# 13thISE_ver6.net
KiCad netlist of a schematic drawn in EAGLE
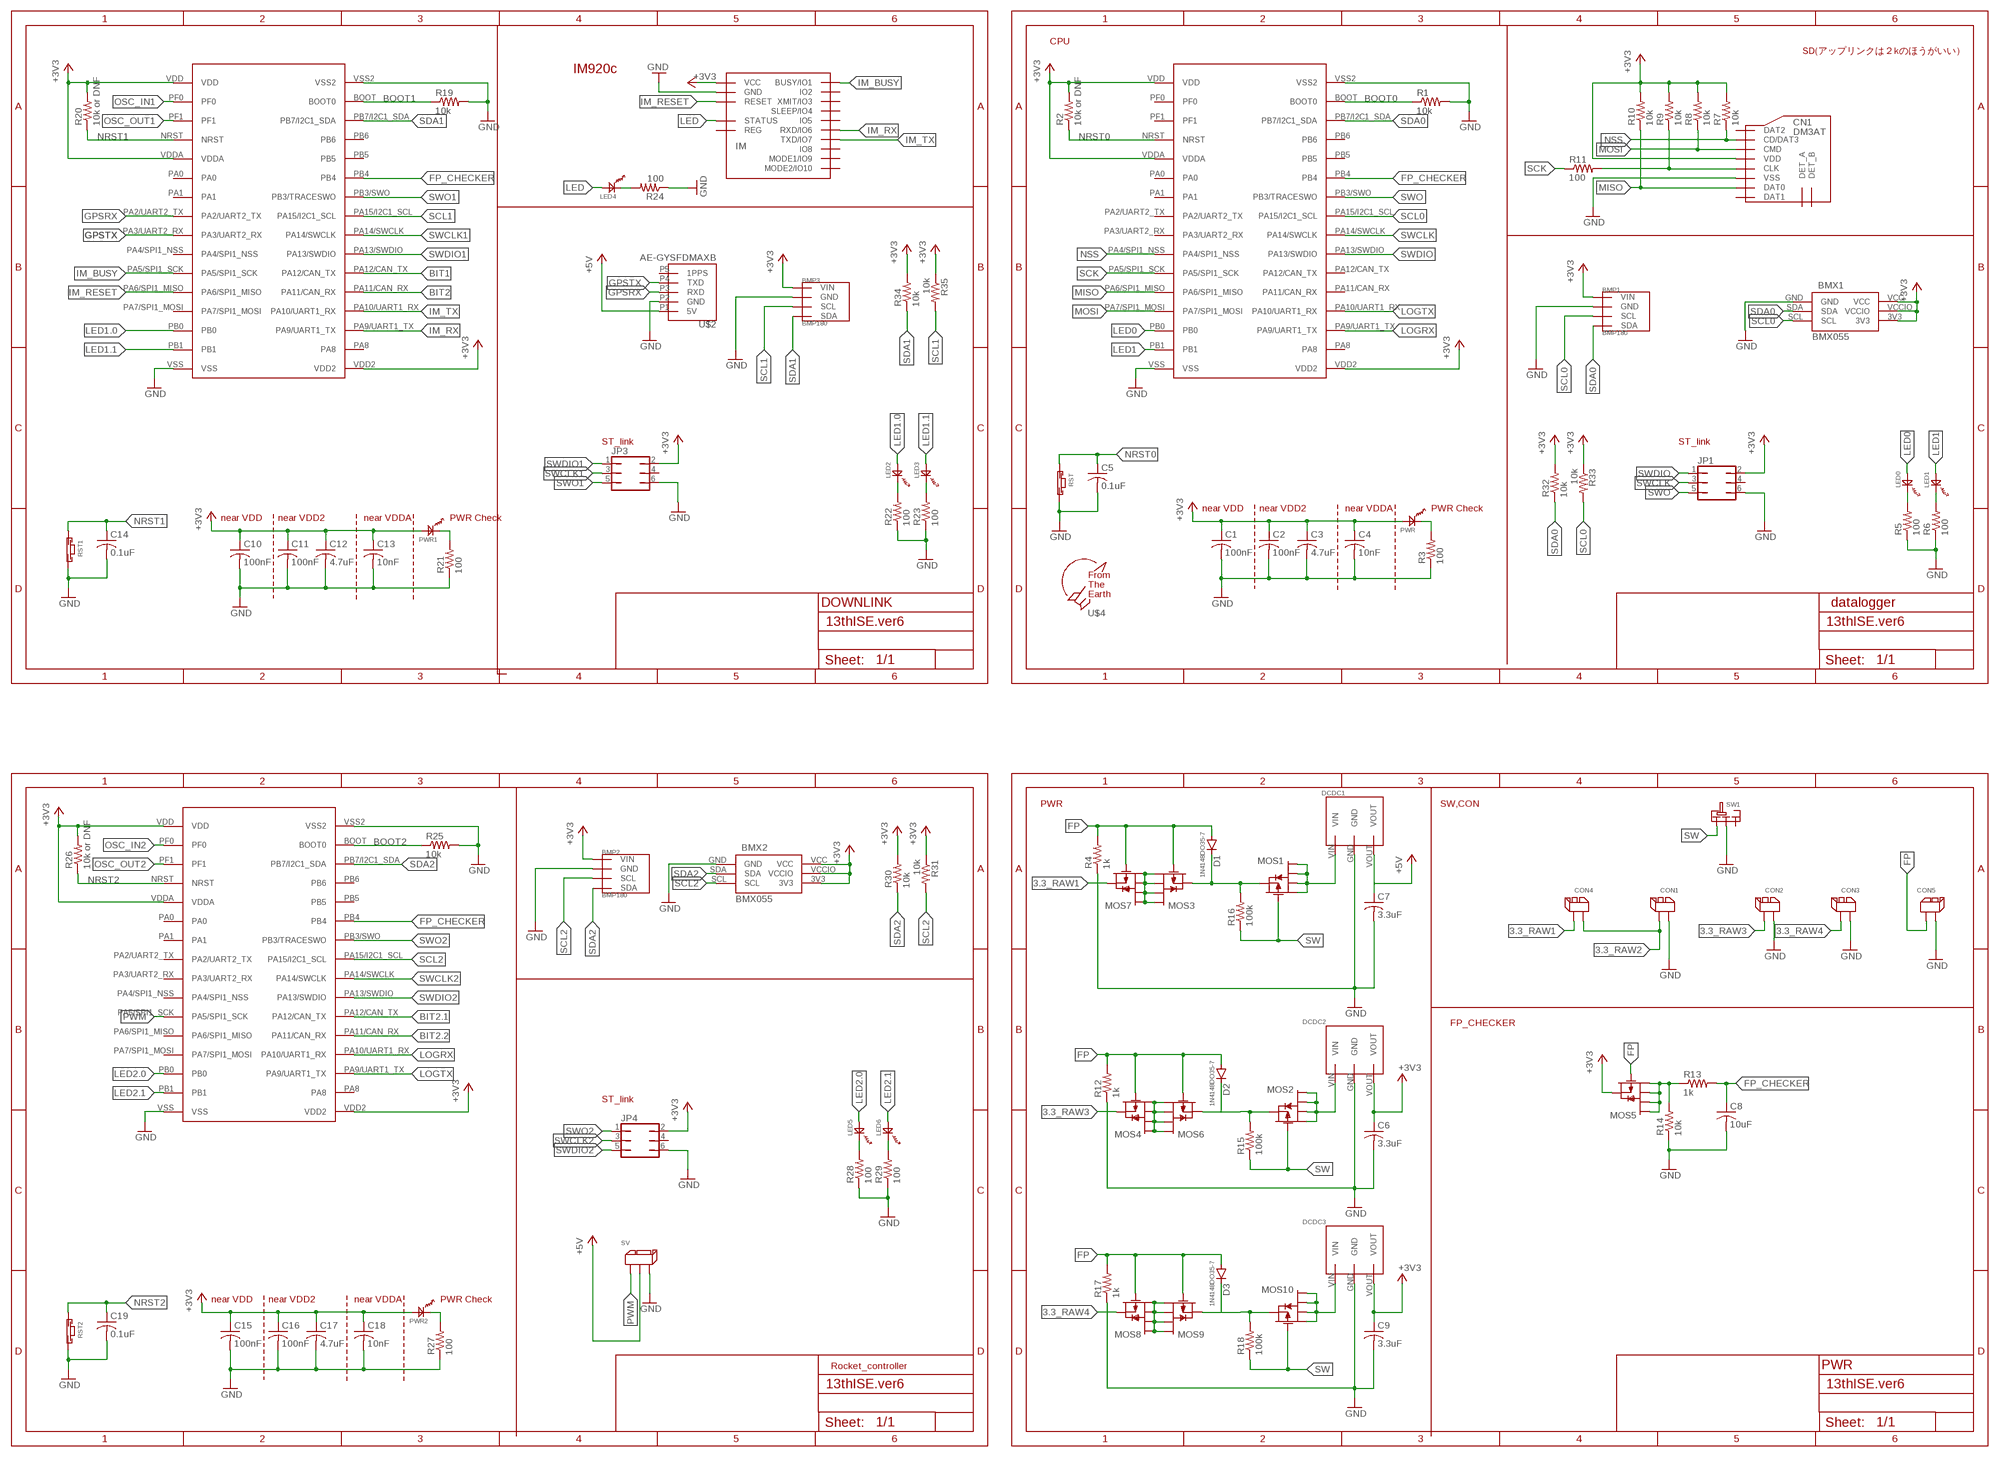
[diagram p0: schematic, sheet 1]

(export (version "E")
  (design (tool "Eeschema 10.0.6"))
  (components
    (comp (ref "BMP1")
      (value "BMP180")
      (footprint "eagle-import:GY-68")
      (libsource (lib "eagle-import") (part "BMP180"))
    )
    (comp (ref "BMP2")
      (value "BMP180")
      (footprint "eagle-import:GY-68")
      (libsource (lib "eagle-import") (part "BMP180"))
    )
    (comp (ref "BMP3")
      (value "BMP180")
      (footprint "eagle-import:GY-68")
      (libsource (lib "eagle-import") (part "BMP180"))
    )
    (comp (ref "BMX1")
      (value "BMX055")
      (footprint "eagle-import:BMX055")
      (libsource (lib "eagle-import") (part "BMX055"))
    )
    (comp (ref "BMX2")
      (value "BMX055")
      (footprint "eagle-import:BMX055")
      (libsource (lib "eagle-import") (part "BMX055"))
    )
    (comp (ref "C1")
      (value "100nF")
      (footprint "eagle-import:C1608")
      (libsource (lib "eagle-import") (part "C-USC1608"))
    )
    (comp (ref "C2")
      (value "100nF")
      (footprint "eagle-import:C1608")
      (libsource (lib "eagle-import") (part "C-USC1608"))
    )
    (comp (ref "C3")
      (value "4.7uF")
      (footprint "eagle-import:C1608")
      (libsource (lib "eagle-import") (part "C-USC1608"))
    )
    (comp (ref "C4")
      (value "10nF")
      (footprint "eagle-import:C1608")
      (libsource (lib "eagle-import") (part "C-USC1608"))
    )
    (comp (ref "C5")
      (value "0.1uF")
      (footprint "eagle-import:C1608")
      (libsource (lib "eagle-import") (part "C-USC1608"))
    )
    (comp (ref "C6")
      (value "3.3uF")
      (footprint "eagle-import:C0603")
      (libsource (lib "eagle-import") (part "C-USC0603"))
    )
    (comp (ref "C7")
      (value "3.3uF")
      (footprint "eagle-import:C0603")
      (libsource (lib "eagle-import") (part "C-USC0603"))
    )
    (comp (ref "C8")
      (value "10uF")
      (footprint "eagle-import:C0603")
      (libsource (lib "eagle-import") (part "C-USC0603"))
    )
    (comp (ref "C9")
      (value "3.3uF")
      (footprint "eagle-import:C0603")
      (libsource (lib "eagle-import") (part "C-USC0603"))
    )
    (comp (ref "C10")
      (value "100nF")
      (footprint "eagle-import:C1608")
      (libsource (lib "eagle-import") (part "C-USC1608"))
    )
    (comp (ref "C11")
      (value "100nF")
      (footprint "eagle-import:C1608")
      (libsource (lib "eagle-import") (part "C-USC1608"))
    )
    (comp (ref "C12")
      (value "4.7uF")
      (footprint "eagle-import:C1608")
      (libsource (lib "eagle-import") (part "C-USC1608"))
    )
    (comp (ref "C13")
      (value "10nF")
      (footprint "eagle-import:C1608")
      (libsource (lib "eagle-import") (part "C-USC1608"))
    )
    (comp (ref "C14")
      (value "0.1uF")
      (footprint "eagle-import:C1608")
      (libsource (lib "eagle-import") (part "C-USC1608"))
    )
    (comp (ref "C15")
      (value "100nF")
      (footprint "eagle-import:C1608")
      (libsource (lib "eagle-import") (part "C-USC1608"))
    )
    (comp (ref "C16")
      (value "100nF")
      (footprint "eagle-import:C1608")
      (libsource (lib "eagle-import") (part "C-USC1608"))
    )
    (comp (ref "C17")
      (value "4.7uF")
      (footprint "eagle-import:C1608")
      (libsource (lib "eagle-import") (part "C-USC1608"))
    )
    (comp (ref "C18")
      (value "10nF")
      (footprint "eagle-import:C1608")
      (libsource (lib "eagle-import") (part "C-USC1608"))
    )
    (comp (ref "C19")
      (value "0.1uF")
      (footprint "eagle-import:C1608")
      (libsource (lib "eagle-import") (part "C-USC1608"))
    )
    (comp (ref "CN1")
      (value "DM3AT")
      (footprint "eagle-import:DM3AT")
      (libsource (lib "eagle-import") (part "DM3AT"))
    )
    (comp (ref "CON1")
      (value "2PIN")
      (footprint "eagle-import:2PIN")
      (libsource (lib "eagle-import") (part "2PIN"))
    )
    (comp (ref "CON2")
      (value "2PIN")
      (footprint "eagle-import:2PIN")
      (libsource (lib "eagle-import") (part "2PIN"))
    )
    (comp (ref "CON3")
      (value "2PIN")
      (footprint "eagle-import:2PIN")
      (libsource (lib "eagle-import") (part "2PIN"))
    )
    (comp (ref "CON4")
      (value "2PIN")
      (footprint "eagle-import:2PIN")
      (libsource (lib "eagle-import") (part "2PIN"))
    )
    (comp (ref "CON5")
      (value "2PIN")
      (footprint "eagle-import:2PIN")
      (libsource (lib "eagle-import") (part "2PIN"))
    )
    (comp (ref "D1")
      (value "1N4148DO35-7")
      (footprint "eagle-import:DO35-7")
      (libsource (lib "eagle-import") (part "1N4148DO35-7"))
    )
    (comp (ref "D2")
      (value "1N4148DO35-7")
      (footprint "eagle-import:DO35-7")
      (libsource (lib "eagle-import") (part "1N4148DO35-7"))
    )
    (comp (ref "D3")
      (value "1N4148DO35-7")
      (footprint "eagle-import:DO35-7")
      (libsource (lib "eagle-import") (part "1N4148DO35-7"))
    )
    (comp (ref "DCDC1")
      (value "5V1A_M78AR05-1")
      (footprint "eagle-import:5V1A_M78AR05-1")
      (libsource (lib "eagle-import") (part "5V1A_M78AR05-1"))
    )
    (comp (ref "DCDC2")
      (value "3.3V1A_M78AR033-1")
      (footprint "eagle-import:3.3V1A_M78AR033-1")
      (libsource (lib "eagle-import") (part "3.3V1A_M78AR033-1"))
    )
    (comp (ref "DCDC3")
      (value "3.3V1A_M78AR033-1")
      (footprint "eagle-import:3.3V1A_M78AR033-1")
      (libsource (lib "eagle-import") (part "3.3V1A_M78AR033-1"))
    )
    (comp (ref "IM")
      (value "IM920C")
      (footprint "eagle-import:IM920C")
      (libsource (lib "eagle-import") (part "IM920C"))
    )
    (comp (ref "JP1")
      (value "JP3Q")
      (footprint "eagle-import:JP3Q")
      (libsource (lib "eagle-import") (part "JP3Q"))
    )
    (comp (ref "JP3")
      (value "JP3Q")
      (footprint "eagle-import:JP3Q")
      (libsource (lib "eagle-import") (part "JP3Q"))
    )
    (comp (ref "JP4")
      (value "JP3Q")
      (footprint "eagle-import:JP3Q")
      (libsource (lib "eagle-import") (part "JP3Q"))
    )
    (comp (ref "LED0")
      (value "OSXX1608C1A")
      (footprint "eagle-import:OSXX1608C1A")
      (libsource (lib "eagle-import") (part "OSXX1608C1A"))
    )
    (comp (ref "LED1")
      (value "OSXX1608C1A")
      (footprint "eagle-import:OSXX1608C1A")
      (libsource (lib "eagle-import") (part "OSXX1608C1A"))
    )
    (comp (ref "LED2")
      (value "OSXX1608C1A")
      (footprint "eagle-import:OSXX1608C1A")
      (libsource (lib "eagle-import") (part "OSXX1608C1A"))
    )
    (comp (ref "LED3")
      (value "OSXX1608C1A")
      (footprint "eagle-import:OSXX1608C1A")
      (libsource (lib "eagle-import") (part "OSXX1608C1A"))
    )
    (comp (ref "LED4")
      (value "OSXX1608C1A")
      (footprint "eagle-import:OSXX1608C1A")
      (libsource (lib "eagle-import") (part "OSXX1608C1A"))
    )
    (comp (ref "LED5")
      (value "OSXX1608C1A")
      (footprint "eagle-import:OSXX1608C1A")
      (libsource (lib "eagle-import") (part "OSXX1608C1A"))
    )
    (comp (ref "LED6")
      (value "OSXX1608C1A")
      (footprint "eagle-import:OSXX1608C1A")
      (libsource (lib "eagle-import") (part "OSXX1608C1A"))
    )
    (comp (ref "MOS1")
      (value "PCH_SSM6J808R")
      (footprint "eagle-import:SSM6J808R")
      (libsource (lib "eagle-import") (part "PCH_SSM6J808R"))
    )
    (comp (ref "MOS2")
      (value "PCH_SSM6J808R")
      (footprint "eagle-import:SSM6J808R")
      (libsource (lib "eagle-import") (part "PCH_SSM6J808R"))
    )
    (comp (ref "MOS3")
      (value "PCH_SSM6J808R")
      (footprint "eagle-import:SSM6J808R")
      (libsource (lib "eagle-import") (part "PCH_SSM6J808R"))
    )
    (comp (ref "MOS4")
      (value "PCH_SSM6J808R")
      (footprint "eagle-import:SSM6J808R")
      (libsource (lib "eagle-import") (part "PCH_SSM6J808R"))
    )
    (comp (ref "MOS5")
      (value "PCH_SSM6J808R")
      (footprint "eagle-import:SSM6J808R")
      (libsource (lib "eagle-import") (part "PCH_SSM6J808R"))
    )
    (comp (ref "MOS6")
      (value "PCH_SSM6J808R")
      (footprint "eagle-import:SSM6J808R")
      (libsource (lib "eagle-import") (part "PCH_SSM6J808R"))
    )
    (comp (ref "MOS7")
      (value "PCH_SSM6J808R")
      (footprint "eagle-import:SSM6J808R")
      (libsource (lib "eagle-import") (part "PCH_SSM6J808R"))
    )
    (comp (ref "MOS8")
      (value "PCH_SSM6J808R")
      (footprint "eagle-import:SSM6J808R")
      (libsource (lib "eagle-import") (part "PCH_SSM6J808R"))
    )
    (comp (ref "MOS9")
      (value "PCH_SSM6J808R")
      (footprint "eagle-import:SSM6J808R")
      (libsource (lib "eagle-import") (part "PCH_SSM6J808R"))
    )
    (comp (ref "MOS10")
      (value "PCH_SSM6J808R")
      (footprint "eagle-import:SSM6J808R")
      (libsource (lib "eagle-import") (part "PCH_SSM6J808R"))
    )
    (comp (ref "PWR")
      (value "OSXX1608C1A")
      (footprint "eagle-import:OSXX1608C1A")
      (libsource (lib "eagle-import") (part "OSXX1608C1A"))
    )
    (comp (ref "PWR1")
      (value "OSXX1608C1A")
      (footprint "eagle-import:OSXX1608C1A")
      (libsource (lib "eagle-import") (part "OSXX1608C1A"))
    )
    (comp (ref "PWR2")
      (value "OSXX1608C1A")
      (footprint "eagle-import:OSXX1608C1A")
      (libsource (lib "eagle-import") (part "OSXX1608C1A"))
    )
    (comp (ref "R1")
      (value "10k")
      (footprint "eagle-import:R0603")
      (libsource (lib "eagle-import") (part "R-US_R0603"))
    )
    (comp (ref "R2")
      (value "10k or DNF")
      (footprint "eagle-import:R0603")
      (libsource (lib "eagle-import") (part "R-US_R0603"))
    )
    (comp (ref "R3")
      (value "100")
      (footprint "eagle-import:R0603")
      (libsource (lib "eagle-import") (part "R-US_R0603"))
    )
    (comp (ref "R4")
      (value "1k")
      (footprint "eagle-import:R0603")
      (libsource (lib "eagle-import") (part "R-US_R0603"))
    )
    (comp (ref "R5")
      (value "100")
      (footprint "eagle-import:R0603")
      (libsource (lib "eagle-import") (part "R-US_R0603"))
    )
    (comp (ref "R6")
      (value "100")
      (footprint "eagle-import:R0603")
      (libsource (lib "eagle-import") (part "R-US_R0603"))
    )
    (comp (ref "R7")
      (value "10k")
      (footprint "eagle-import:R0603")
      (libsource (lib "eagle-import") (part "R-US_R0603"))
    )
    (comp (ref "R8")
      (value "10k")
      (footprint "eagle-import:R0603")
      (libsource (lib "eagle-import") (part "R-US_R0603"))
    )
    (comp (ref "R9")
      (value "10k")
      (footprint "eagle-import:R0603")
      (libsource (lib "eagle-import") (part "R-US_R0603"))
    )
    (comp (ref "R10")
      (value "10k")
      (footprint "eagle-import:R0603")
      (libsource (lib "eagle-import") (part "R-US_R0603"))
    )
    (comp (ref "R11")
      (value "100")
      (footprint "eagle-import:R0603")
      (libsource (lib "eagle-import") (part "R-US_R0603"))
    )
    (comp (ref "R12")
      (value "1k")
      (footprint "eagle-import:R0603")
      (libsource (lib "eagle-import") (part "R-US_R0603"))
    )
    (comp (ref "R13")
      (value "1k")
      (footprint "eagle-import:R0603")
      (libsource (lib "eagle-import") (part "R-US_R0603"))
    )
    (comp (ref "R14")
      (value "10k")
      (footprint "eagle-import:R0603")
      (libsource (lib "eagle-import") (part "R-US_R0603"))
    )
    (comp (ref "R15")
      (value "100k")
      (footprint "eagle-import:R0603")
      (libsource (lib "eagle-import") (part "R-US_R0603"))
    )
    (comp (ref "R16")
      (value "100k")
      (footprint "eagle-import:R0603")
      (libsource (lib "eagle-import") (part "R-US_R0603"))
    )
    (comp (ref "R17")
      (value "1k")
      (footprint "eagle-import:R0603")
      (libsource (lib "eagle-import") (part "R-US_R0603"))
    )
    (comp (ref "R18")
      (value "100k")
      (footprint "eagle-import:R0603")
      (libsource (lib "eagle-import") (part "R-US_R0603"))
    )
    (comp (ref "R19")
      (value "10k")
      (footprint "eagle-import:R0603")
      (libsource (lib "eagle-import") (part "R-US_R0603"))
    )
    (comp (ref "R20")
      (value "10k or DNF")
      (footprint "eagle-import:R0603")
      (libsource (lib "eagle-import") (part "R-US_R0603"))
    )
    (comp (ref "R21")
      (value "100")
      (footprint "eagle-import:R0603")
      (libsource (lib "eagle-import") (part "R-US_R0603"))
    )
    (comp (ref "R22")
      (value "100")
      (footprint "eagle-import:R0603")
      (libsource (lib "eagle-import") (part "R-US_R0603"))
    )
    (comp (ref "R23")
      (value "100")
      (footprint "eagle-import:R0603")
      (libsource (lib "eagle-import") (part "R-US_R0603"))
    )
    (comp (ref "R24")
      (value "100")
      (footprint "eagle-import:R0603")
      (libsource (lib "eagle-import") (part "R-US_R0603"))
    )
    (comp (ref "R25")
      (value "10k")
      (footprint "eagle-import:R0603")
      (libsource (lib "eagle-import") (part "R-US_R0603"))
    )
    (comp (ref "R26")
      (value "10k or DNF")
      (footprint "eagle-import:R0603")
      (libsource (lib "eagle-import") (part "R-US_R0603"))
    )
    (comp (ref "R27")
      (value "100")
      (footprint "eagle-import:R0603")
      (libsource (lib "eagle-import") (part "R-US_R0603"))
    )
    (comp (ref "R28")
      (value "100")
      (footprint "eagle-import:R0603")
      (libsource (lib "eagle-import") (part "R-US_R0603"))
    )
    (comp (ref "R29")
      (value "100")
      (footprint "eagle-import:R0603")
      (libsource (lib "eagle-import") (part "R-US_R0603"))
    )
    (comp (ref "R30")
      (value "10k")
      (footprint "eagle-import:R0603")
      (libsource (lib "eagle-import") (part "R-US_R0603"))
    )
    (comp (ref "R31")
      (value "10k")
      (footprint "eagle-import:R0603")
      (libsource (lib "eagle-import") (part "R-US_R0603"))
    )
    (comp (ref "R32")
      (value "10k")
      (footprint "eagle-import:R0603")
      (libsource (lib "eagle-import") (part "R-US_R0603"))
    )
    (comp (ref "R33")
      (value "10k")
      (footprint "eagle-import:R0603")
      (libsource (lib "eagle-import") (part "R-US_R0603"))
    )
    (comp (ref "R34")
      (value "10k")
      (footprint "eagle-import:R0603")
      (libsource (lib "eagle-import") (part "R-US_R0603"))
    )
    (comp (ref "R35")
      (value "10k")
      (footprint "eagle-import:R0603")
      (libsource (lib "eagle-import") (part "R-US_R0603"))
    )
    (comp (ref "RST")
      (value "TVAF06-A020B-R")
      (footprint "eagle-import:TVAF06-A020B-R")
      (libsource (lib "eagle-import") (part "TVAF06-A020B-R"))
    )
    (comp (ref "RST1")
      (value "TVAF06-A020B-R")
      (footprint "eagle-import:TVAF06-A020B-R")
      (libsource (lib "eagle-import") (part "TVAF06-A020B-R"))
    )
    (comp (ref "RST2")
      (value "TVAF06-A020B-R")
      (footprint "eagle-import:TVAF06-A020B-R")
      (libsource (lib "eagle-import") (part "TVAF06-A020B-R"))
    )
    (comp (ref "STM0")
      (value "STM32F303K8")
      (footprint "eagle-import:STM32F303K8")
      (libsource (lib "eagle-import") (part "STM32F303K8"))
    )
    (comp (ref "STM1")
      (value "STM32F303K8")
      (footprint "eagle-import:STM32F303K8")
      (libsource (lib "eagle-import") (part "STM32F303K8"))
    )
    (comp (ref "SV")
      (value "3PIN")
      (footprint "eagle-import:3PIN")
      (libsource (lib "eagle-import") (part "3PIN"))
    )
    (comp (ref "SW1")
      (value "SRIDE_SWITCH")
      (footprint "eagle-import:SRIDE_SWITCH")
      (libsource (lib "eagle-import") (part "SRIDE_SWITCH"))
    )
    (comp (ref "U$1")
      (value "STM32F303K8")
      (footprint "eagle-import:STM32F303K8")
      (libsource (lib "eagle-import") (part "STM32F303K8"))
    )
    (comp (ref "U$2")
      (value "AE-GYSFDMAXB")
      (footprint "eagle-import:AE-GYSFDMAXB")
      (libsource (lib "eagle-import") (part "AE-GYSFDMAXB"))
    )
    (comp (ref "U$4")
      (value "F.T.E.LOGO")
      (footprint "eagle-import:LOGO")
      (libsource (lib "eagle-import") (part "F.T.E.LOGO"))
    )
  )
  (nets
    (net (code "1") (name "+3V3") (class "Default")
      (node (ref "BMP1") (pin "P1") (pinfunction "VIN_P1") (pintype "bidirectional"))
      (node (ref "BMP2") (pin "P1") (pinfunction "VIN_P1") (pintype "bidirectional"))
      (node (ref "BMP3") (pin "P1") (pinfunction "VIN_P1") (pintype "bidirectional"))
      (node (ref "BMX1") (pin "3V3") (pinfunction "3V3_3V3") (pintype "power_in"))
      (node (ref "BMX1") (pin "VCC") (pinfunction "VCC_VCC") (pintype "power_in"))
      (node (ref "BMX1") (pin "VCCIO") (pinfunction "VCCIO_VCCIO") (pintype "power_in"))
      (node (ref "BMX2") (pin "3V3") (pinfunction "3V3_3V3") (pintype "power_in"))
      (node (ref "BMX2") (pin "VCC") (pinfunction "VCC_VCC") (pintype "power_in"))
      (node (ref "BMX2") (pin "VCCIO") (pinfunction "VCCIO_VCCIO") (pintype "power_in"))
      (node (ref "C1") (pin "1") (pinfunction "1_1") (pintype "passive"))
      (node (ref "C10") (pin "1") (pinfunction "1_1") (pintype "passive"))
      (node (ref "C11") (pin "1") (pinfunction "1_1") (pintype "passive"))
      (node (ref "C12") (pin "1") (pinfunction "1_1") (pintype "passive"))
      (node (ref "C13") (pin "1") (pinfunction "1_1") (pintype "passive"))
      (node (ref "C15") (pin "1") (pinfunction "1_1") (pintype "passive"))
      (node (ref "C16") (pin "1") (pinfunction "1_1") (pintype "passive"))
      (node (ref "C17") (pin "1") (pinfunction "1_1") (pintype "passive"))
      (node (ref "C18") (pin "1") (pinfunction "1_1") (pintype "passive"))
      (node (ref "C2") (pin "1") (pinfunction "1_1") (pintype "passive"))
      (node (ref "C3") (pin "1") (pinfunction "1_1") (pintype "passive"))
      (node (ref "C4") (pin "1") (pinfunction "1_1") (pintype "passive"))
      (node (ref "C6") (pin "1") (pinfunction "1_1") (pintype "passive"))
      (node (ref "C9") (pin "1") (pinfunction "1_1") (pintype "passive"))
      (node (ref "CN1") (pin "VDD") (pinfunction "VDD_VDD") (pintype "bidirectional"))
      (node (ref "DCDC2") (pin "VOUT") (pinfunction "VOUT_VOUT") (pintype "bidirectional"))
      (node (ref "DCDC3") (pin "VOUT") (pinfunction "VOUT_VOUT") (pintype "bidirectional"))
      (node (ref "IM") (pin "$P17") (pinfunction "VCC_$P17") (pintype "bidirectional"))
      (node (ref "JP1") (pin "2") (pinfunction "2_2") (pintype "passive"))
      (node (ref "JP3") (pin "2") (pinfunction "2_2") (pintype "passive"))
      (node (ref "JP4") (pin "2") (pinfunction "2_2") (pintype "passive"))
      (node (ref "MOS5") (pin "4") (pinfunction "4_4") (pintype "bidirectional"))
      (node (ref "PWR") (pin "AN") (pinfunction "AN_AN") (pintype "bidirectional"))
      (node (ref "PWR1") (pin "AN") (pinfunction "AN_AN") (pintype "bidirectional"))
      (node (ref "PWR2") (pin "AN") (pinfunction "AN_AN") (pintype "bidirectional"))
      (node (ref "R10") (pin "2") (pinfunction "2_2") (pintype "passive"))
      (node (ref "R2") (pin "2") (pinfunction "2_2") (pintype "passive"))
      (node (ref "R20") (pin "2") (pinfunction "2_2") (pintype "passive"))
      (node (ref "R26") (pin "2") (pinfunction "2_2") (pintype "passive"))
      (node (ref "R30") (pin "2") (pinfunction "2_2") (pintype "passive"))
      (node (ref "R31") (pin "1") (pinfunction "1_1") (pintype "passive"))
      (node (ref "R32") (pin "2") (pinfunction "2_2") (pintype "passive"))
      (node (ref "R33") (pin "1") (pinfunction "1_1") (pintype "passive"))
      (node (ref "R34") (pin "2") (pinfunction "2_2") (pintype "passive"))
      (node (ref "R35") (pin "1") (pinfunction "1_1") (pintype "passive"))
      (node (ref "R7") (pin "2") (pinfunction "2_2") (pintype "passive"))
      (node (ref "R8") (pin "2") (pinfunction "2_2") (pintype "passive"))
      (node (ref "R9") (pin "2") (pinfunction "2_2") (pintype "passive"))
      (node (ref "STM0") (pin "VDD") (pinfunction "VDD_VDD") (pintype "power_in"))
      (node (ref "STM0") (pin "VDD2") (pinfunction "VDD2_VDD2") (pintype "power_in"))
      (node (ref "STM0") (pin "VDDA") (pinfunction "VDDA_VDDA") (pintype "power_in"))
      (node (ref "STM1") (pin "VDD") (pinfunction "VDD_VDD") (pintype "power_in"))
      (node (ref "STM1") (pin "VDD2") (pinfunction "VDD2_VDD2") (pintype "power_in"))
      (node (ref "STM1") (pin "VDDA") (pinfunction "VDDA_VDDA") (pintype "power_in"))
      (node (ref "U$1") (pin "VDD") (pinfunction "VDD_VDD") (pintype "power_in"))
      (node (ref "U$1") (pin "VDD2") (pinfunction "VDD2_VDD2") (pintype "power_in"))
      (node (ref "U$1") (pin "VDDA") (pinfunction "VDDA_VDDA") (pintype "power_in"))
    )
    (net (code "2") (name "+5V") (class "Default")
      (node (ref "C7") (pin "1") (pinfunction "1_1") (pintype "passive"))
      (node (ref "DCDC1") (pin "VOUT") (pinfunction "VOUT_VOUT") (pintype "bidirectional"))
      (node (ref "SV") (pin "P$2") (pinfunction "P$2_P$2") (pintype "bidirectional"))
      (node (ref "U$2") (pin "P1") (pinfunction "5V_P1") (pintype "bidirectional"))
    )
    (net (code "3") (name "/BOOT0") (class "Default")
      (node (ref "R1") (pin "1") (pinfunction "1_1") (pintype "passive"))
      (node (ref "STM0") (pin "BOOT") (pinfunction "BOOT0_BOOT") (pintype "bidirectional"))
    )
    (net (code "4") (name "/BOOT1") (class "Default")
      (node (ref "R19") (pin "1") (pinfunction "1_1") (pintype "passive"))
      (node (ref "STM1") (pin "BOOT") (pinfunction "BOOT0_BOOT") (pintype "bidirectional"))
    )
    (net (code "5") (name "/BOOT2") (class "Default")
      (node (ref "R25") (pin "1") (pinfunction "1_1") (pintype "passive"))
      (node (ref "U$1") (pin "BOOT") (pinfunction "BOOT0_BOOT") (pintype "bidirectional"))
    )
    (net (code "6") (name "3.3_RAW1") (class "Default")
      (node (ref "CON4") (pin "P$2") (pinfunction "P$2_P$2") (pintype "bidirectional"))
      (node (ref "MOS7") (pin "4") (pinfunction "4_4") (pintype "bidirectional"))
    )
    (net (code "7") (name "3.3_RAW2") (class "Default")
      (node (ref "CON1") (pin "P$2") (pinfunction "P$2_P$2") (pintype "bidirectional"))
      (node (ref "CON4") (pin "P$1") (pinfunction "P$1_P$1") (pintype "bidirectional"))
    )
    (net (code "8") (name "3.3_RAW3") (class "Default")
      (node (ref "CON2") (pin "P$2") (pinfunction "P$2_P$2") (pintype "bidirectional"))
      (node (ref "MOS4") (pin "4") (pinfunction "4_4") (pintype "bidirectional"))
    )
    (net (code "9") (name "3.3_RAW4") (class "Default")
      (node (ref "CON3") (pin "P$2") (pinfunction "P$2_P$2") (pintype "bidirectional"))
      (node (ref "MOS8") (pin "4") (pinfunction "4_4") (pintype "bidirectional"))
    )
    (net (code "10") (name "BIT1") (class "Default")
      (node (ref "STM1") (pin "PA12/CAN_TX") (pinfunction "PA12/CAN_TX_PA12/CAN_TX") (pintype "bidirectional"))
    )
    (net (code "11") (name "BIT2") (class "Default")
      (node (ref "STM1") (pin "PA11/CAN_RX") (pinfunction "PA11/CAN_RX_PA11/CAN_RX") (pintype "bidirectional"))
    )
    (net (code "12") (name "BIT2.1") (class "Default")
      (node (ref "U$1") (pin "PA12/CAN_TX") (pinfunction "PA12/CAN_TX_PA12/CAN_TX") (pintype "bidirectional"))
    )
    (net (code "13") (name "BIT2.2") (class "Default")
      (node (ref "U$1") (pin "PA11/CAN_RX") (pinfunction "PA11/CAN_RX_PA11/CAN_RX") (pintype "bidirectional"))
    )
    (net (code "14") (name "FP") (class "Default")
      (node (ref "CON5") (pin "P$1") (pinfunction "P$1_P$1") (pintype "bidirectional"))
      (node (ref "D1") (pin "A") (pinfunction "A_A") (pintype "passive"))
      (node (ref "D2") (pin "A") (pinfunction "A_A") (pintype "passive"))
      (node (ref "D3") (pin "A") (pinfunction "A_A") (pintype "passive"))
      (node (ref "MOS3") (pin "3") (pinfunction "3_3") (pintype "bidirectional"))
      (node (ref "MOS4") (pin "3") (pinfunction "3_3") (pintype "bidirectional"))
      (node (ref "MOS5") (pin "3") (pinfunction "3_3") (pintype "bidirectional"))
      (node (ref "MOS6") (pin "3") (pinfunction "3_3") (pintype "bidirectional"))
      (node (ref "MOS7") (pin "3") (pinfunction "3_3") (pintype "bidirectional"))
      (node (ref "MOS8") (pin "3") (pinfunction "3_3") (pintype "bidirectional"))
      (node (ref "MOS9") (pin "3") (pinfunction "3_3") (pintype "bidirectional"))
      (node (ref "R12") (pin "2") (pinfunction "2_2") (pintype "passive"))
      (node (ref "R17") (pin "2") (pinfunction "2_2") (pintype "passive"))
      (node (ref "R4") (pin "2") (pinfunction "2_2") (pintype "passive"))
    )
    (net (code "15") (name "FP_CHECKER") (class "Default")
      (node (ref "C8") (pin "1") (pinfunction "1_1") (pintype "passive"))
      (node (ref "R13") (pin "2") (pinfunction "2_2") (pintype "passive"))
      (node (ref "STM0") (pin "PB4") (pinfunction "PB4_PB4") (pintype "bidirectional"))
      (node (ref "STM1") (pin "PB4") (pinfunction "PB4_PB4") (pintype "bidirectional"))
      (node (ref "U$1") (pin "PB4") (pinfunction "PB4_PB4") (pintype "bidirectional"))
    )
    (net (code "16") (name "GND") (class "Default")
      (node (ref "BMP1") (pin "P2") (pinfunction "GND_P2") (pintype "bidirectional"))
      (node (ref "BMP2") (pin "P2") (pinfunction "GND_P2") (pintype "bidirectional"))
      (node (ref "BMP3") (pin "P2") (pinfunction "GND_P2") (pintype "bidirectional"))
      (node (ref "BMX1") (pin "GND") (pinfunction "GND_GND") (pintype "power_in"))
      (node (ref "BMX2") (pin "GND") (pinfunction "GND_GND") (pintype "power_in"))
      (node (ref "C1") (pin "2") (pinfunction "2_2") (pintype "passive"))
      (node (ref "C10") (pin "2") (pinfunction "2_2") (pintype "passive"))
      (node (ref "C11") (pin "2") (pinfunction "2_2") (pintype "passive"))
      (node (ref "C12") (pin "2") (pinfunction "2_2") (pintype "passive"))
      (node (ref "C13") (pin "2") (pinfunction "2_2") (pintype "passive"))
      (node (ref "C14") (pin "2") (pinfunction "2_2") (pintype "passive"))
      (node (ref "C15") (pin "2") (pinfunction "2_2") (pintype "passive"))
      (node (ref "C16") (pin "2") (pinfunction "2_2") (pintype "passive"))
      (node (ref "C17") (pin "2") (pinfunction "2_2") (pintype "passive"))
      (node (ref "C18") (pin "2") (pinfunction "2_2") (pintype "passive"))
      (node (ref "C19") (pin "2") (pinfunction "2_2") (pintype "passive"))
      (node (ref "C2") (pin "2") (pinfunction "2_2") (pintype "passive"))
      (node (ref "C3") (pin "2") (pinfunction "2_2") (pintype "passive"))
      (node (ref "C4") (pin "2") (pinfunction "2_2") (pintype "passive"))
      (node (ref "C5") (pin "2") (pinfunction "2_2") (pintype "passive"))
      (node (ref "C6") (pin "2") (pinfunction "2_2") (pintype "passive"))
      (node (ref "C7") (pin "2") (pinfunction "2_2") (pintype "passive"))
      (node (ref "C8") (pin "2") (pinfunction "2_2") (pintype "passive"))
      (node (ref "C9") (pin "2") (pinfunction "2_2") (pintype "passive"))
      (node (ref "CN1") (pin "VSS") (pinfunction "VSS_VSS") (pintype "bidirectional"))
      (node (ref "CON1") (pin "P$1") (pinfunction "P$1_P$1") (pintype "bidirectional"))
      (node (ref "CON2") (pin "P$1") (pinfunction "P$1_P$1") (pintype "bidirectional"))
      (node (ref "CON3") (pin "P$1") (pinfunction "P$1_P$1") (pintype "bidirectional"))
      (node (ref "CON5") (pin "P$2") (pinfunction "P$2_P$2") (pintype "bidirectional"))
      (node (ref "DCDC1") (pin "GND") (pinfunction "GND_GND") (pintype "bidirectional"))
      (node (ref "DCDC2") (pin "GND") (pinfunction "GND_GND") (pintype "bidirectional"))
      (node (ref "DCDC3") (pin "GND") (pinfunction "GND_GND") (pintype "bidirectional"))
      (node (ref "IM") (pin "$P18") (pinfunction "GND_$P18") (pintype "bidirectional"))
      (node (ref "JP1") (pin "6") (pinfunction "6_6") (pintype "passive"))
      (node (ref "JP3") (pin "6") (pinfunction "6_6") (pintype "passive"))
      (node (ref "JP4") (pin "6") (pinfunction "6_6") (pintype "passive"))
      (node (ref "R1") (pin "2") (pinfunction "2_2") (pintype "passive"))
      (node (ref "R12") (pin "1") (pinfunction "1_1") (pintype "passive"))
      (node (ref "R14") (pin "1") (pinfunction "1_1") (pintype "passive"))
      (node (ref "R17") (pin "1") (pinfunction "1_1") (pintype "passive"))
      (node (ref "R19") (pin "2") (pinfunction "2_2") (pintype "passive"))
      (node (ref "R21") (pin "1") (pinfunction "1_1") (pintype "passive"))
      (node (ref "R22") (pin "1") (pinfunction "1_1") (pintype "passive"))
      (node (ref "R23") (pin "1") (pinfunction "1_1") (pintype "passive"))
      (node (ref "R24") (pin "1") (pinfunction "1_1") (pintype "passive"))
      (node (ref "R25") (pin "2") (pinfunction "2_2") (pintype "passive"))
      (node (ref "R27") (pin "1") (pinfunction "1_1") (pintype "passive"))
      (node (ref "R28") (pin "1") (pinfunction "1_1") (pintype "passive"))
      (node (ref "R29") (pin "1") (pinfunction "1_1") (pintype "passive"))
      (node (ref "R3") (pin "1") (pinfunction "1_1") (pintype "passive"))
      (node (ref "R4") (pin "1") (pinfunction "1_1") (pintype "passive"))
      (node (ref "R5") (pin "1") (pinfunction "1_1") (pintype "passive"))
      (node (ref "R6") (pin "1") (pinfunction "1_1") (pintype "passive"))
      (node (ref "RST") (pin "P$2") (pinfunction "P$2_P$2") (pintype "bidirectional"))
      (node (ref "RST1") (pin "P$2") (pinfunction "P$2_P$2") (pintype "bidirectional"))
      (node (ref "RST2") (pin "P$2") (pinfunction "P$2_P$2") (pintype "bidirectional"))
      (node (ref "STM0") (pin "VSS") (pinfunction "VSS_VSS") (pintype "power_in"))
      (node (ref "STM0") (pin "VSS2") (pinfunction "VSS2_VSS2") (pintype "power_in"))
      (node (ref "STM1") (pin "VSS") (pinfunction "VSS_VSS") (pintype "power_in"))
      (node (ref "STM1") (pin "VSS2") (pinfunction "VSS2_VSS2") (pintype "power_in"))
      (node (ref "SV") (pin "P$3") (pinfunction "P$3_P$3") (pintype "bidirectional"))
      (node (ref "SW1") (pin "LR") (pinfunction "LR_LR") (pintype "bidirectional"))
      (node (ref "U$1") (pin "VSS") (pinfunction "VSS_VSS") (pintype "power_in"))
      (node (ref "U$1") (pin "VSS2") (pinfunction "VSS2_VSS2") (pintype "power_in"))
      (node (ref "U$2") (pin "P2") (pinfunction "GND_P2") (pintype "bidirectional"))
    )
    (net (code "17") (name "GPSRX") (class "Default")
      (node (ref "STM1") (pin "PA2/UART2_TX") (pinfunction "PA2/UART2_TX_PA2/UART2_TX") (pintype "bidirectional"))
      (node (ref "U$2") (pin "P3") (pinfunction "RXD_P3") (pintype "bidirectional"))
    )
    (net (code "18") (name "GPSTX") (class "Default")
      (node (ref "STM1") (pin "PA3/UART2_RX") (pinfunction "PA3/UART2_RX_PA3/UART2_RX") (pintype "bidirectional"))
      (node (ref "U$2") (pin "P4") (pinfunction "TXD_P4") (pintype "bidirectional"))
    )
    (net (code "19") (name "IM_BUSY") (class "Default")
      (node (ref "IM") (pin "$P1") (pinfunction "BUSY/IO1_$P1") (pintype "bidirectional"))
      (node (ref "STM1") (pin "PA5/SPI1_SCK") (pinfunction "PA5/SPI1_SCK_PA5/SPI1_SCK") (pintype "bidirectional"))
    )
    (net (code "20") (name "IM_RESET") (class "Default")
      (node (ref "IM") (pin "$P19") (pinfunction "RESET_$P19") (pintype "bidirectional"))
      (node (ref "STM1") (pin "PA6/SPI1_MISO") (pinfunction "PA6/SPI1_MISO_PA6/SPI1_MISO") (pintype "bidirectional"))
    )
    (net (code "21") (name "IM_RX") (class "Default")
      (node (ref "IM") (pin "$P6") (pinfunction "RXD/IO6_$P6") (pintype "bidirectional"))
      (node (ref "STM1") (pin "PA9/UART1_TX") (pinfunction "PA9/UART1_TX_PA9/UART1_TX") (pintype "bidirectional"))
    )
    (net (code "22") (name "IM_TX") (class "Default")
      (node (ref "IM") (pin "$P7") (pinfunction "TXD/IO7_$P7") (pintype "bidirectional"))
      (node (ref "STM1") (pin "PA10/UART1_RX") (pinfunction "PA10/UART1_RX_PA10/UART1_RX") (pintype "bidirectional"))
    )
    (net (code "23") (name "LED") (class "Default")
      (node (ref "IM") (pin "$P15") (pinfunction "STATUS_$P15") (pintype "bidirectional"))
      (node (ref "LED4") (pin "AN") (pinfunction "AN_AN") (pintype "bidirectional"))
    )
    (net (code "24") (name "LED0") (class "Default")
      (node (ref "LED0") (pin "AN") (pinfunction "AN_AN") (pintype "bidirectional"))
      (node (ref "STM0") (pin "PB0") (pinfunction "PB0_PB0") (pintype "bidirectional"))
    )
    (net (code "25") (name "LED1") (class "Default")
      (node (ref "LED1") (pin "AN") (pinfunction "AN_AN") (pintype "bidirectional"))
      (node (ref "STM0") (pin "PB1") (pinfunction "PB1_PB1") (pintype "bidirectional"))
    )
    (net (code "26") (name "LED1.0") (class "Default")
      (node (ref "LED2") (pin "AN") (pinfunction "AN_AN") (pintype "bidirectional"))
      (node (ref "STM1") (pin "PB0") (pinfunction "PB0_PB0") (pintype "bidirectional"))
    )
    (net (code "27") (name "LED1.1") (class "Default")
      (node (ref "LED3") (pin "AN") (pinfunction "AN_AN") (pintype "bidirectional"))
      (node (ref "STM1") (pin "PB1") (pinfunction "PB1_PB1") (pintype "bidirectional"))
    )
    (net (code "28") (name "LED2.0") (class "Default")
      (node (ref "LED5") (pin "AN") (pinfunction "AN_AN") (pintype "bidirectional"))
      (node (ref "U$1") (pin "PB0") (pinfunction "PB0_PB0") (pintype "bidirectional"))
    )
    (net (code "29") (name "LED2.1") (class "Default")
      (node (ref "LED6") (pin "AN") (pinfunction "AN_AN") (pintype "bidirectional"))
      (node (ref "U$1") (pin "PB1") (pinfunction "PB1_PB1") (pintype "bidirectional"))
    )
    (net (code "30") (name "LOGRX") (class "Default")
      (node (ref "STM0") (pin "PA9/UART1_TX") (pinfunction "PA9/UART1_TX_PA9/UART1_TX") (pintype "bidirectional"))
      (node (ref "U$1") (pin "PA10/UART1_RX") (pinfunction "PA10/UART1_RX_PA10/UART1_RX") (pintype "bidirectional"))
    )
    (net (code "31") (name "LOGTX") (class "Default")
      (node (ref "STM0") (pin "PA10/UART1_RX") (pinfunction "PA10/UART1_RX_PA10/UART1_RX") (pintype "bidirectional"))
      (node (ref "U$1") (pin "PA9/UART1_TX") (pinfunction "PA9/UART1_TX_PA9/UART1_TX") (pintype "bidirectional"))
    )
    (net (code "32") (name "MISO") (class "Default")
      (node (ref "CN1") (pin "DAT0") (pinfunction "DAT0_DAT0") (pintype "bidirectional"))
      (node (ref "R10") (pin "1") (pinfunction "1_1") (pintype "passive"))
      (node (ref "STM0") (pin "PA6/SPI1_MISO") (pinfunction "PA6/SPI1_MISO_PA6/SPI1_MISO") (pintype "bidirectional"))
    )
    (net (code "33") (name "MOSI") (class "Default")
      (node (ref "CN1") (pin "CMD") (pinfunction "CMD_CMD") (pintype "bidirectional"))
      (node (ref "R8") (pin "1") (pinfunction "1_1") (pintype "passive"))
      (node (ref "STM0") (pin "PA7/SPI1_MOSI") (pinfunction "PA7/SPI1_MOSI_PA7/SPI1_MOSI") (pintype "bidirectional"))
    )
    (net (code "34") (name "NRST0") (class "Default")
      (node (ref "C5") (pin "1") (pinfunction "1_1") (pintype "passive"))
      (node (ref "R2") (pin "1") (pinfunction "1_1") (pintype "passive"))
      (node (ref "RST") (pin "P$1") (pinfunction "P$1_P$1") (pintype "bidirectional"))
      (node (ref "STM0") (pin "NRST") (pinfunction "NRST_NRST") (pintype "bidirectional"))
    )
    (net (code "35") (name "NRST1") (class "Default")
      (node (ref "C14") (pin "1") (pinfunction "1_1") (pintype "passive"))
      (node (ref "R20") (pin "1") (pinfunction "1_1") (pintype "passive"))
      (node (ref "RST1") (pin "P$1") (pinfunction "P$1_P$1") (pintype "bidirectional"))
      (node (ref "STM1") (pin "NRST") (pinfunction "NRST_NRST") (pintype "bidirectional"))
    )
    (net (code "36") (name "NRST2") (class "Default")
      (node (ref "C19") (pin "1") (pinfunction "1_1") (pintype "passive"))
      (node (ref "R26") (pin "1") (pinfunction "1_1") (pintype "passive"))
      (node (ref "RST2") (pin "P$1") (pinfunction "P$1_P$1") (pintype "bidirectional"))
      (node (ref "U$1") (pin "NRST") (pinfunction "NRST_NRST") (pintype "bidirectional"))
    )
    (net (code "37") (name "NSS") (class "Default")
      (node (ref "CN1") (pin "CD/DAT3") (pinfunction "CD/DAT3_CD/DAT3") (pintype "bidirectional"))
      (node (ref "R7") (pin "1") (pinfunction "1_1") (pintype "passive"))
      (node (ref "STM0") (pin "PA4/SPI1_NSS") (pinfunction "PA4/SPI1_NSS_PA4/SPI1_NSS") (pintype "bidirectional"))
    )
    (net (code "38") (name "Net-(CN1-PadCLK)") (class "Default")
      (node (ref "CN1") (pin "CLK") (pinfunction "CLK_CLK") (pintype "bidirectional"))
      (node (ref "R11") (pin "2") (pinfunction "2_2") (pintype "passive"))
      (node (ref "R9") (pin "1") (pinfunction "1_1") (pintype "passive"))
    )
    (net (code "39") (name "Net-(D1-PadC)") (class "Default")
      (node (ref "D1") (pin "C") (pinfunction "C_C") (pintype "passive"))
      (node (ref "MOS1") (pin "4") (pinfunction "4_4") (pintype "bidirectional"))
      (node (ref "MOS3") (pin "4") (pinfunction "4_4") (pintype "bidirectional"))
      (node (ref "R16") (pin "2") (pinfunction "2_2") (pintype "passive"))
    )
    (net (code "40") (name "Net-(D2-PadC)") (class "Default")
      (node (ref "D2") (pin "C") (pinfunction "C_C") (pintype "passive"))
      (node (ref "MOS2") (pin "4") (pinfunction "4_4") (pintype "bidirectional"))
      (node (ref "MOS6") (pin "4") (pinfunction "4_4") (pintype "bidirectional"))
      (node (ref "R15") (pin "2") (pinfunction "2_2") (pintype "passive"))
    )
    (net (code "41") (name "Net-(D3-PadC)") (class "Default")
      (node (ref "D3") (pin "C") (pinfunction "C_C") (pintype "passive"))
      (node (ref "MOS10") (pin "4") (pinfunction "4_4") (pintype "bidirectional"))
      (node (ref "MOS9") (pin "4") (pinfunction "4_4") (pintype "bidirectional"))
      (node (ref "R18") (pin "2") (pinfunction "2_2") (pintype "passive"))
    )
    (net (code "42") (name "Net-(DCDC1-PadVIN)") (class "Default")
      (node (ref "DCDC1") (pin "VIN") (pinfunction "VIN_VIN") (pintype "bidirectional"))
      (node (ref "MOS1") (pin "1") (pinfunction "1_1") (pintype "bidirectional"))
      (node (ref "MOS1") (pin "2") (pinfunction "2_2") (pintype "bidirectional"))
      (node (ref "MOS1") (pin "5") (pinfunction "5_5") (pintype "bidirectional"))
      (node (ref "MOS1") (pin "6") (pinfunction "6_6") (pintype "bidirectional"))
    )
    (net (code "43") (name "Net-(DCDC2-PadVIN)") (class "Default")
      (node (ref "DCDC2") (pin "VIN") (pinfunction "VIN_VIN") (pintype "bidirectional"))
      (node (ref "MOS2") (pin "1") (pinfunction "1_1") (pintype "bidirectional"))
      (node (ref "MOS2") (pin "2") (pinfunction "2_2") (pintype "bidirectional"))
      (node (ref "MOS2") (pin "5") (pinfunction "5_5") (pintype "bidirectional"))
      (node (ref "MOS2") (pin "6") (pinfunction "6_6") (pintype "bidirectional"))
    )
    (net (code "44") (name "Net-(DCDC3-PadVIN)") (class "Default")
      (node (ref "DCDC3") (pin "VIN") (pinfunction "VIN_VIN") (pintype "bidirectional"))
      (node (ref "MOS10") (pin "1") (pinfunction "1_1") (pintype "bidirectional"))
      (node (ref "MOS10") (pin "2") (pinfunction "2_2") (pintype "bidirectional"))
      (node (ref "MOS10") (pin "5") (pinfunction "5_5") (pintype "bidirectional"))
      (node (ref "MOS10") (pin "6") (pinfunction "6_6") (pintype "bidirectional"))
    )
    (net (code "45") (name "Net-(LED0-PadCT)") (class "Default")
      (node (ref "LED0") (pin "CT") (pinfunction "CT_CT") (pintype "bidirectional"))
      (node (ref "R5") (pin "2") (pinfunction "2_2") (pintype "passive"))
    )
    (net (code "46") (name "Net-(LED1-PadCT)") (class "Default")
      (node (ref "LED1") (pin "CT") (pinfunction "CT_CT") (pintype "bidirectional"))
      (node (ref "R6") (pin "2") (pinfunction "2_2") (pintype "passive"))
    )
    (net (code "47") (name "Net-(LED2-PadCT)") (class "Default")
      (node (ref "LED2") (pin "CT") (pinfunction "CT_CT") (pintype "bidirectional"))
      (node (ref "R22") (pin "2") (pinfunction "2_2") (pintype "passive"))
    )
    (net (code "48") (name "Net-(LED3-PadCT)") (class "Default")
      (node (ref "LED3") (pin "CT") (pinfunction "CT_CT") (pintype "bidirectional"))
      (node (ref "R23") (pin "2") (pinfunction "2_2") (pintype "passive"))
    )
    (net (code "49") (name "Net-(LED4-PadCT)") (class "Default")
      (node (ref "LED4") (pin "CT") (pinfunction "CT_CT") (pintype "bidirectional"))
      (node (ref "R24") (pin "2") (pinfunction "2_2") (pintype "passive"))
    )
    (net (code "50") (name "Net-(LED5-PadCT)") (class "Default")
      (node (ref "LED5") (pin "CT") (pinfunction "CT_CT") (pintype "bidirectional"))
      (node (ref "R28") (pin "2") (pinfunction "2_2") (pintype "passive"))
    )
    (net (code "51") (name "Net-(LED6-PadCT)") (class "Default")
      (node (ref "LED6") (pin "CT") (pinfunction "CT_CT") (pintype "bidirectional"))
      (node (ref "R29") (pin "2") (pinfunction "2_2") (pintype "passive"))
    )
    (net (code "52") (name "Net-(MOS3-Pad1)") (class "Default")
      (node (ref "MOS3") (pin "1") (pinfunction "1_1") (pintype "bidirectional"))
      (node (ref "MOS3") (pin "2") (pinfunction "2_2") (pintype "bidirectional"))
      (node (ref "MOS3") (pin "5") (pinfunction "5_5") (pintype "bidirectional"))
      (node (ref "MOS3") (pin "6") (pinfunction "6_6") (pintype "bidirectional"))
      (node (ref "MOS7") (pin "1") (pinfunction "1_1") (pintype "bidirectional"))
      (node (ref "MOS7") (pin "2") (pinfunction "2_2") (pintype "bidirectional"))
      (node (ref "MOS7") (pin "5") (pinfunction "5_5") (pintype "bidirectional"))
      (node (ref "MOS7") (pin "6") (pinfunction "6_6") (pintype "bidirectional"))
    )
    (net (code "53") (name "Net-(MOS4-Pad1)") (class "Default")
      (node (ref "MOS4") (pin "1") (pinfunction "1_1") (pintype "bidirectional"))
      (node (ref "MOS4") (pin "2") (pinfunction "2_2") (pintype "bidirectional"))
      (node (ref "MOS4") (pin "5") (pinfunction "5_5") (pintype "bidirectional"))
      (node (ref "MOS4") (pin "6") (pinfunction "6_6") (pintype "bidirectional"))
      (node (ref "MOS6") (pin "1") (pinfunction "1_1") (pintype "bidirectional"))
      (node (ref "MOS6") (pin "2") (pinfunction "2_2") (pintype "bidirectional"))
      (node (ref "MOS6") (pin "5") (pinfunction "5_5") (pintype "bidirectional"))
      (node (ref "MOS6") (pin "6") (pinfunction "6_6") (pintype "bidirectional"))
    )
    (net (code "54") (name "Net-(MOS5-Pad1)") (class "Default")
      (node (ref "MOS5") (pin "1") (pinfunction "1_1") (pintype "bidirectional"))
      (node (ref "MOS5") (pin "2") (pinfunction "2_2") (pintype "bidirectional"))
      (node (ref "MOS5") (pin "5") (pinfunction "5_5") (pintype "bidirectional"))
      (node (ref "MOS5") (pin "6") (pinfunction "6_6") (pintype "bidirectional"))
      (node (ref "R13") (pin "1") (pinfunction "1_1") (pintype "passive"))
      (node (ref "R14") (pin "2") (pinfunction "2_2") (pintype "passive"))
    )
    (net (code "55") (name "Net-(MOS8-Pad1)") (class "Default")
      (node (ref "MOS8") (pin "1") (pinfunction "1_1") (pintype "bidirectional"))
      (node (ref "MOS8") (pin "2") (pinfunction "2_2") (pintype "bidirectional"))
      (node (ref "MOS8") (pin "5") (pinfunction "5_5") (pintype "bidirectional"))
      (node (ref "MOS8") (pin "6") (pinfunction "6_6") (pintype "bidirectional"))
      (node (ref "MOS9") (pin "1") (pinfunction "1_1") (pintype "bidirectional"))
      (node (ref "MOS9") (pin "2") (pinfunction "2_2") (pintype "bidirectional"))
      (node (ref "MOS9") (pin "5") (pinfunction "5_5") (pintype "bidirectional"))
      (node (ref "MOS9") (pin "6") (pinfunction "6_6") (pintype "bidirectional"))
    )
    (net (code "56") (name "Net-(PWR-PadCT)") (class "Default")
      (node (ref "PWR") (pin "CT") (pinfunction "CT_CT") (pintype "bidirectional"))
      (node (ref "R3") (pin "2") (pinfunction "2_2") (pintype "passive"))
    )
    (net (code "57") (name "Net-(PWR1-PadCT)") (class "Default")
      (node (ref "PWR1") (pin "CT") (pinfunction "CT_CT") (pintype "bidirectional"))
      (node (ref "R21") (pin "2") (pinfunction "2_2") (pintype "passive"))
    )
    (net (code "58") (name "Net-(PWR2-PadCT)") (class "Default")
      (node (ref "PWR2") (pin "CT") (pinfunction "CT_CT") (pintype "bidirectional"))
      (node (ref "R27") (pin "2") (pinfunction "2_2") (pintype "passive"))
    )
    (net (code "59") (name "OSC_IN1") (class "Default")
      (node (ref "STM1") (pin "PF0") (pinfunction "PF0_PF0") (pintype "bidirectional"))
    )
    (net (code "60") (name "OSC_IN2") (class "Default")
      (node (ref "U$1") (pin "PF0") (pinfunction "PF0_PF0") (pintype "bidirectional"))
    )
    (net (code "61") (name "OSC_OUT1") (class "Default")
      (node (ref "STM1") (pin "PF1") (pinfunction "PF1_PF1") (pintype "bidirectional"))
    )
    (net (code "62") (name "OSC_OUT2") (class "Default")
      (node (ref "U$1") (pin "PF1") (pinfunction "PF1_PF1") (pintype "bidirectional"))
    )
    (net (code "63") (name "PWM") (class "Default")
      (node (ref "SV") (pin "P$1") (pinfunction "P$1_P$1") (pintype "bidirectional"))
      (node (ref "U$1") (pin "PA5/SPI1_SCK") (pinfunction "PA5/SPI1_SCK_PA5/SPI1_SCK") (pintype "bidirectional"))
    )
    (net (code "64") (name "SCK") (class "Default")
      (node (ref "R11") (pin "1") (pinfunction "1_1") (pintype "passive"))
      (node (ref "STM0") (pin "PA5/SPI1_SCK") (pinfunction "PA5/SPI1_SCK_PA5/SPI1_SCK") (pintype "bidirectional"))
    )
    (net (code "65") (name "SCL0") (class "Default")
      (node (ref "BMP1") (pin "P3") (pinfunction "SCL_P3") (pintype "bidirectional"))
      (node (ref "BMX1") (pin "SCL") (pinfunction "SCL_SCL") (pintype "bidirectional"))
      (node (ref "R33") (pin "2") (pinfunction "2_2") (pintype "passive"))
      (node (ref "STM0") (pin "PA15/I2C1_SCL") (pinfunction "PA15/I2C1_SCL_PA15/I2C1_SCL") (pintype "bidirectional"))
    )
    (net (code "66") (name "SCL1") (class "Default")
      (node (ref "BMP3") (pin "P3") (pinfunction "SCL_P3") (pintype "bidirectional"))
      (node (ref "R35") (pin "2") (pinfunction "2_2") (pintype "passive"))
      (node (ref "STM1") (pin "PA15/I2C1_SCL") (pinfunction "PA15/I2C1_SCL_PA15/I2C1_SCL") (pintype "bidirectional"))
    )
    (net (code "67") (name "SCL2") (class "Default")
      (node (ref "BMP2") (pin "P3") (pinfunction "SCL_P3") (pintype "bidirectional"))
      (node (ref "BMX2") (pin "SCL") (pinfunction "SCL_SCL") (pintype "bidirectional"))
      (node (ref "R31") (pin "2") (pinfunction "2_2") (pintype "passive"))
      (node (ref "U$1") (pin "PA15/I2C1_SCL") (pinfunction "PA15/I2C1_SCL_PA15/I2C1_SCL") (pintype "bidirectional"))
    )
    (net (code "68") (name "SDA0") (class "Default")
      (node (ref "BMP1") (pin "P4") (pinfunction "SDA_P4") (pintype "bidirectional"))
      (node (ref "BMX1") (pin "SDA") (pinfunction "SDA_SDA") (pintype "bidirectional"))
      (node (ref "R32") (pin "1") (pinfunction "1_1") (pintype "passive"))
      (node (ref "STM0") (pin "PB7/I2C1_SDA") (pinfunction "PB7/I2C1_SDA_PB7/I2C1_SDA") (pintype "bidirectional"))
    )
    (net (code "69") (name "SDA1") (class "Default")
      (node (ref "BMP3") (pin "P4") (pinfunction "SDA_P4") (pintype "bidirectional"))
      (node (ref "R34") (pin "1") (pinfunction "1_1") (pintype "passive"))
      (node (ref "STM1") (pin "PB7/I2C1_SDA") (pinfunction "PB7/I2C1_SDA_PB7/I2C1_SDA") (pintype "bidirectional"))
    )
    (net (code "70") (name "SDA2") (class "Default")
      (node (ref "BMP2") (pin "P4") (pinfunction "SDA_P4") (pintype "bidirectional"))
      (node (ref "BMX2") (pin "SDA") (pinfunction "SDA_SDA") (pintype "bidirectional"))
      (node (ref "R30") (pin "1") (pinfunction "1_1") (pintype "passive"))
      (node (ref "U$1") (pin "PB7/I2C1_SDA") (pinfunction "PB7/I2C1_SDA_PB7/I2C1_SDA") (pintype "bidirectional"))
    )
    (net (code "71") (name "SW") (class "Default")
      (node (ref "MOS1") (pin "3") (pinfunction "3_3") (pintype "bidirectional"))
      (node (ref "MOS10") (pin "3") (pinfunction "3_3") (pintype "bidirectional"))
      (node (ref "MOS2") (pin "3") (pinfunction "3_3") (pintype "bidirectional"))
      (node (ref "R15") (pin "1") (pinfunction "1_1") (pintype "passive"))
      (node (ref "R16") (pin "1") (pinfunction "1_1") (pintype "passive"))
      (node (ref "R18") (pin "1") (pinfunction "1_1") (pintype "passive"))
      (node (ref "SW1") (pin "L") (pinfunction "L_L") (pintype "bidirectional"))
    )
    (net (code "72") (name "SWCLK") (class "Default")
      (node (ref "JP1") (pin "3") (pinfunction "3_3") (pintype "passive"))
      (node (ref "STM0") (pin "PA14/SWCLK") (pinfunction "PA14/SWCLK_PA14/SWCLK") (pintype "bidirectional"))
    )
    (net (code "73") (name "SWCLK1") (class "Default")
      (node (ref "JP3") (pin "3") (pinfunction "3_3") (pintype "passive"))
      (node (ref "STM1") (pin "PA14/SWCLK") (pinfunction "PA14/SWCLK_PA14/SWCLK") (pintype "bidirectional"))
    )
    (net (code "74") (name "SWCLK2") (class "Default")
      (node (ref "JP4") (pin "3") (pinfunction "3_3") (pintype "passive"))
      (node (ref "U$1") (pin "PA14/SWCLK") (pinfunction "PA14/SWCLK_PA14/SWCLK") (pintype "bidirectional"))
    )
    (net (code "75") (name "SWDIO") (class "Default")
      (node (ref "JP1") (pin "1") (pinfunction "1_1") (pintype "passive"))
      (node (ref "STM0") (pin "PA13/SWDIO") (pinfunction "PA13/SWDIO_PA13/SWDIO") (pintype "bidirectional"))
    )
    (net (code "76") (name "SWDIO1") (class "Default")
      (node (ref "JP3") (pin "1") (pinfunction "1_1") (pintype "passive"))
      (node (ref "STM1") (pin "PA13/SWDIO") (pinfunction "PA13/SWDIO_PA13/SWDIO") (pintype "bidirectional"))
    )
    (net (code "77") (name "SWDIO2") (class "Default")
      (node (ref "JP4") (pin "5") (pinfunction "5_5") (pintype "passive"))
      (node (ref "U$1") (pin "PA13/SWDIO") (pinfunction "PA13/SWDIO_PA13/SWDIO") (pintype "bidirectional"))
    )
    (net (code "78") (name "SWO") (class "Default")
      (node (ref "JP1") (pin "5") (pinfunction "5_5") (pintype "passive"))
      (node (ref "STM0") (pin "PB3/SWO") (pinfunction "PB3/TRACESWO_PB3/SWO") (pintype "bidirectional"))
    )
    (net (code "79") (name "SWO1") (class "Default")
      (node (ref "JP3") (pin "5") (pinfunction "5_5") (pintype "passive"))
      (node (ref "STM1") (pin "PB3/SWO") (pinfunction "PB3/TRACESWO_PB3/SWO") (pintype "bidirectional"))
    )
    (net (code "80") (name "SWO2") (class "Default")
      (node (ref "JP4") (pin "1") (pinfunction "1_1") (pintype "passive"))
      (node (ref "U$1") (pin "PB3/SWO") (pinfunction "PB3/TRACESWO_PB3/SWO") (pintype "bidirectional"))
    )
    (net (code "81") (name "unconnected-(CN1-PadDAT1)") (class "Default")
      (node (ref "CN1") (pin "DAT1") (pinfunction "DAT1_DAT1") (pintype "bidirectional"))
    )
    (net (code "82") (name "unconnected-(CN1-PadDAT2)") (class "Default")
      (node (ref "CN1") (pin "DAT2") (pinfunction "DAT2_DAT2") (pintype "bidirectional"))
    )
    (net (code "83") (name "unconnected-(CN1-PadDET_A)") (class "Default")
      (node (ref "CN1") (pin "DET_A") (pinfunction "DET_A_DET_A") (pintype "bidirectional"))
    )
    (net (code "84") (name "unconnected-(CN1-PadDET_B)") (class "Default")
      (node (ref "CN1") (pin "DET_B") (pinfunction "DET_B_DET_B") (pintype "bidirectional"))
    )
    (net (code "85") (name "unconnected-(IM-IO2-Pad$P2)") (class "Default")
      (node (ref "IM") (pin "$P2") (pinfunction "IO2_$P2") (pintype "bidirectional"))
    )
    (net (code "86") (name "unconnected-(IM-IO5-Pad$P5)") (class "Default")
      (node (ref "IM") (pin "$P5") (pinfunction "IO5_$P5") (pintype "bidirectional"))
    )
    (net (code "87") (name "unconnected-(IM-IO8-Pad$P8)") (class "Default")
      (node (ref "IM") (pin "$P8") (pinfunction "IO8_$P8") (pintype "bidirectional"))
    )
    (net (code "88") (name "unconnected-(IM-MODE1{slash}IO9-Pad$P9)") (class "Default")
      (node (ref "IM") (pin "$P9") (pinfunction "MODE1/IO9_$P9") (pintype "bidirectional"))
    )
    (net (code "89") (name "unconnected-(IM-MODE2{slash}IO10-Pad$P10)") (class "Default")
      (node (ref "IM") (pin "$P10") (pinfunction "MODE2/IO10_$P10") (pintype "bidirectional"))
    )
    (net (code "90") (name "unconnected-(IM-REG-Pad$P16)") (class "Default")
      (node (ref "IM") (pin "$P16") (pinfunction "REG_$P16") (pintype "bidirectional"))
    )
    (net (code "91") (name "unconnected-(IM-SLEEP{slash}IO4-Pad$P4)") (class "Default")
      (node (ref "IM") (pin "$P4") (pinfunction "SLEEP/IO4_$P4") (pintype "bidirectional"))
    )
    (net (code "92") (name "unconnected-(IM-XMIT{slash}IO3-Pad$P3)") (class "Default")
      (node (ref "IM") (pin "$P3") (pinfunction "XMIT/IO3_$P3") (pintype "bidirectional"))
    )
    (net (code "93") (name "unconnected-(JP1-Pad4)") (class "Default")
      (node (ref "JP1") (pin "4") (pinfunction "4_4") (pintype "passive"))
    )
    (net (code "94") (name "unconnected-(JP3-Pad4)") (class "Default")
      (node (ref "JP3") (pin "4") (pinfunction "4_4") (pintype "passive"))
    )
    (net (code "95") (name "unconnected-(JP4-Pad4)") (class "Default")
      (node (ref "JP4") (pin "4") (pinfunction "4_4") (pintype "passive"))
    )
    (net (code "96") (name "unconnected-(STM0-PadPA0)") (class "Default")
      (node (ref "STM0") (pin "PA0") (pinfunction "PA0_PA0") (pintype "bidirectional"))
    )
    (net (code "97") (name "unconnected-(STM0-PadPA1)") (class "Default")
      (node (ref "STM0") (pin "PA1") (pinfunction "PA1_PA1") (pintype "bidirectional"))
    )
    (net (code "98") (name "unconnected-(STM0-PadPA2{slash}UART2_TX)") (class "Default")
      (node (ref "STM0") (pin "PA2/UART2_TX") (pinfunction "PA2/UART2_TX_PA2/UART2_TX") (pintype "bidirectional"))
    )
    (net (code "99") (name "unconnected-(STM0-PadPA3{slash}UART2_RX)") (class "Default")
      (node (ref "STM0") (pin "PA3/UART2_RX") (pinfunction "PA3/UART2_RX_PA3/UART2_RX") (pintype "bidirectional"))
    )
    (net (code "100") (name "unconnected-(STM0-PadPA8)") (class "Default")
      (node (ref "STM0") (pin "PA8") (pinfunction "PA8_PA8") (pintype "bidirectional"))
    )
    (net (code "101") (name "unconnected-(STM0-PadPA11{slash}CAN_RX)") (class "Default")
      (node (ref "STM0") (pin "PA11/CAN_RX") (pinfunction "PA11/CAN_RX_PA11/CAN_RX") (pintype "bidirectional"))
    )
    (net (code "102") (name "unconnected-(STM0-PadPA12{slash}CAN_TX)") (class "Default")
      (node (ref "STM0") (pin "PA12/CAN_TX") (pinfunction "PA12/CAN_TX_PA12/CAN_TX") (pintype "bidirectional"))
    )
    (net (code "103") (name "unconnected-(STM0-PadPB5)") (class "Default")
      (node (ref "STM0") (pin "PB5") (pinfunction "PB5_PB5") (pintype "bidirectional"))
    )
    (net (code "104") (name "unconnected-(STM0-PadPB6)") (class "Default")
      (node (ref "STM0") (pin "PB6") (pinfunction "PB6_PB6") (pintype "bidirectional"))
    )
    (net (code "105") (name "unconnected-(STM0-PadPF0)") (class "Default")
      (node (ref "STM0") (pin "PF0") (pinfunction "PF0_PF0") (pintype "bidirectional"))
    )
    (net (code "106") (name "unconnected-(STM0-PadPF1)") (class "Default")
      (node (ref "STM0") (pin "PF1") (pinfunction "PF1_PF1") (pintype "bidirectional"))
    )
    (net (code "107") (name "unconnected-(STM1-PadPA0)") (class "Default")
      (node (ref "STM1") (pin "PA0") (pinfunction "PA0_PA0") (pintype "bidirectional"))
    )
    (net (code "108") (name "unconnected-(STM1-PadPA1)") (class "Default")
      (node (ref "STM1") (pin "PA1") (pinfunction "PA1_PA1") (pintype "bidirectional"))
    )
    (net (code "109") (name "unconnected-(STM1-PadPA4{slash}SPI1_NSS)") (class "Default")
      (node (ref "STM1") (pin "PA4/SPI1_NSS") (pinfunction "PA4/SPI1_NSS_PA4/SPI1_NSS") (pintype "bidirectional"))
    )
    (net (code "110") (name "unconnected-(STM1-PadPA7{slash}SPI1_MOSI)") (class "Default")
      (node (ref "STM1") (pin "PA7/SPI1_MOSI") (pinfunction "PA7/SPI1_MOSI_PA7/SPI1_MOSI") (pintype "bidirectional"))
    )
    (net (code "111") (name "unconnected-(STM1-PadPA8)") (class "Default")
      (node (ref "STM1") (pin "PA8") (pinfunction "PA8_PA8") (pintype "bidirectional"))
    )
    (net (code "112") (name "unconnected-(STM1-PadPB5)") (class "Default")
      (node (ref "STM1") (pin "PB5") (pinfunction "PB5_PB5") (pintype "bidirectional"))
    )
    (net (code "113") (name "unconnected-(STM1-PadPB6)") (class "Default")
      (node (ref "STM1") (pin "PB6") (pinfunction "PB6_PB6") (pintype "bidirectional"))
    )
    (net (code "114") (name "unconnected-(SW1-PadR)") (class "Default")
      (node (ref "SW1") (pin "R") (pinfunction "R_R") (pintype "bidirectional"))
    )
    (net (code "115") (name "unconnected-(U$1-PadPA0)") (class "Default")
      (node (ref "U$1") (pin "PA0") (pinfunction "PA0_PA0") (pintype "bidirectional"))
    )
    (net (code "116") (name "unconnected-(U$1-PadPA1)") (class "Default")
      (node (ref "U$1") (pin "PA1") (pinfunction "PA1_PA1") (pintype "bidirectional"))
    )
    (net (code "117") (name "unconnected-(U$1-PadPA2{slash}UART2_TX)") (class "Default")
      (node (ref "U$1") (pin "PA2/UART2_TX") (pinfunction "PA2/UART2_TX_PA2/UART2_TX") (pintype "bidirectional"))
    )
    (net (code "118") (name "unconnected-(U$1-PadPA3{slash}UART2_RX)") (class "Default")
      (node (ref "U$1") (pin "PA3/UART2_RX") (pinfunction "PA3/UART2_RX_PA3/UART2_RX") (pintype "bidirectional"))
    )
    (net (code "119") (name "unconnected-(U$1-PadPA4{slash}SPI1_NSS)") (class "Default")
      (node (ref "U$1") (pin "PA4/SPI1_NSS") (pinfunction "PA4/SPI1_NSS_PA4/SPI1_NSS") (pintype "bidirectional"))
    )
    (net (code "120") (name "unconnected-(U$1-PadPA6{slash}SPI1_MISO)") (class "Default")
      (node (ref "U$1") (pin "PA6/SPI1_MISO") (pinfunction "PA6/SPI1_MISO_PA6/SPI1_MISO") (pintype "bidirectional"))
    )
    (net (code "121") (name "unconnected-(U$1-PadPA7{slash}SPI1_MOSI)") (class "Default")
      (node (ref "U$1") (pin "PA7/SPI1_MOSI") (pinfunction "PA7/SPI1_MOSI_PA7/SPI1_MOSI") (pintype "bidirectional"))
    )
    (net (code "122") (name "unconnected-(U$1-PadPA8)") (class "Default")
      (node (ref "U$1") (pin "PA8") (pinfunction "PA8_PA8") (pintype "bidirectional"))
    )
    (net (code "123") (name "unconnected-(U$1-PadPB5)") (class "Default")
      (node (ref "U$1") (pin "PB5") (pinfunction "PB5_PB5") (pintype "bidirectional"))
    )
    (net (code "124") (name "unconnected-(U$1-PadPB6)") (class "Default")
      (node (ref "U$1") (pin "PB6") (pinfunction "PB6_PB6") (pintype "bidirectional"))
    )
    (net (code "125") (name "unconnected-(U$2-1PPS-PadP5)") (class "Default")
      (node (ref "U$2") (pin "P5") (pinfunction "1PPS_P5") (pintype "bidirectional"))
    )
  )
)
